# LB_BIT_1IN_2OUT-XXXL-v03_1_1x.net
KiCad netlist of a schematic drawn in EAGLE
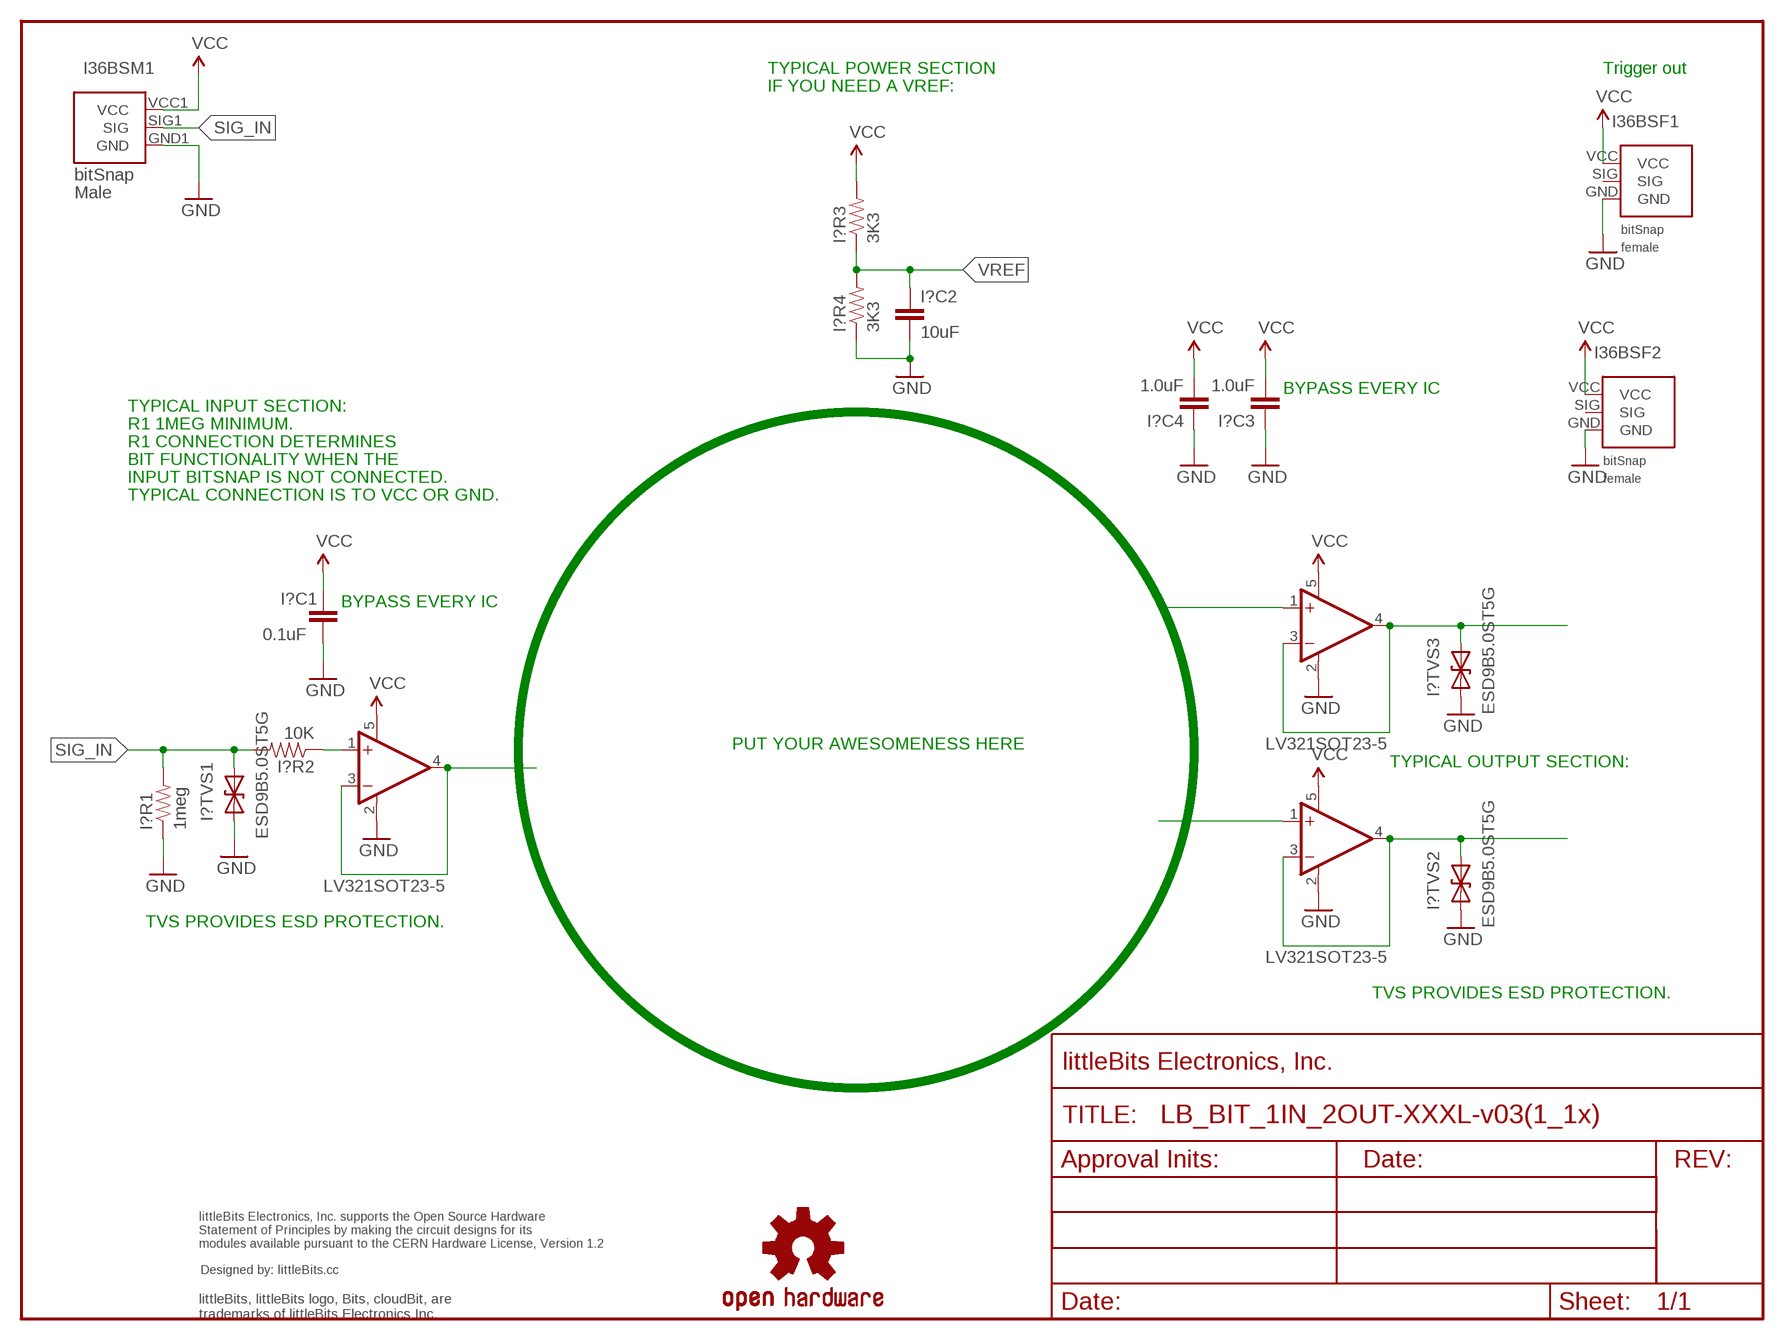
[diagram p0: schematic, sheet 1]

(export (version "E")
  (design (tool "Eeschema 10.0.6"))
  (components
    (comp (ref "FRAME1")
      (value "FRAME-LETTER")
      (footprint "eagle-import:FABDWG01-OHW")
      (libsource (lib "eagle-import") (part "FRAME-LETTER"))
    )
    (comp (ref "I36BSF1")
      (value "BITSNAP_V03_FEMALE")
      (footprint "eagle-import:BITSNAP_V03_FEMALE")
      (libsource (lib "eagle-import") (part "BITSNAP_V03_FEMALE"))
    )
    (comp (ref "I36BSF2")
      (value "BITSNAP_V03_FEMALE")
      (footprint "eagle-import:BITSNAP_V03_FEMALE")
      (libsource (lib "eagle-import") (part "BITSNAP_V03_FEMALE"))
    )
    (comp (ref "I36BSM1")
      (value "BITSNAP_V03_MALE")
      (footprint "eagle-import:BITSNAP_V03_MALE")
      (libsource (lib "eagle-import") (part "BITSNAP_V03_MALE"))
    )
    (comp (ref "I?C1")
      (value "0.1uF")
      (footprint "eagle-import:CAP-0603")
      (libsource (lib "eagle-import") (part "CAPCAP-0603"))
    )
    (comp (ref "I?C2")
      (value "10uF")
      (footprint "eagle-import:CAP-0603")
      (libsource (lib "eagle-import") (part "CAPCAP-0603"))
    )
    (comp (ref "I?C3")
      (value "1.0uF")
      (footprint "eagle-import:CAP-0603")
      (libsource (lib "eagle-import") (part "CAPCAP-0603"))
    )
    (comp (ref "I?C4")
      (value "1.0uF")
      (footprint "eagle-import:CAP-0603")
      (libsource (lib "eagle-import") (part "CAPCAP-0603"))
    )
    (comp (ref "I?R1")
      (value "1meg")
      (footprint "eagle-import:RES-0603")
      (libsource (lib "eagle-import") (part "RESISTOR0603"))
    )
    (comp (ref "I?R2")
      (value "10K")
      (footprint "eagle-import:RES-0603")
      (libsource (lib "eagle-import") (part "RESISTOR0603"))
    )
    (comp (ref "I?R3")
      (value "3K3")
      (footprint "eagle-import:RES-0603")
      (libsource (lib "eagle-import") (part "RESISTOR0603"))
    )
    (comp (ref "I?R4")
      (value "3K3")
      (footprint "eagle-import:RES-0603")
      (libsource (lib "eagle-import") (part "RESISTOR0603"))
    )
    (comp (ref "I?TVS1")
      (value "ESD9B5.0ST5G")
      (footprint "eagle-import:SOD-923")
      (libsource (lib "eagle-import") (part "DIODE-TVSSOD-923"))
    )
    (comp (ref "I?TVS2")
      (value "ESD9B5.0ST5G")
      (footprint "eagle-import:SOD-923")
      (libsource (lib "eagle-import") (part "DIODE-TVSSOD-923"))
    )
    (comp (ref "I?TVS3")
      (value "ESD9B5.0ST5G")
      (footprint "eagle-import:SOD-923")
      (libsource (lib "eagle-import") (part "DIODE-TVSSOD-923"))
    )
    (comp (ref "U$1")
      (value "OSHW-LOGOL")
      (footprint "eagle-import:OSHW-LOGO-L")
      (libsource (lib "eagle-import") (part "OSHW-LOGOL"))
    )
    (comp (ref "U$3")
      (value "OSHWCREDIT")
      (footprint "eagle-import:OSHWCREDIT")
      (libsource (lib "eagle-import") (part "OSHWCREDIT"))
    )
    (comp (ref "U1")
      (value "LV321SOT23-5")
      (footprint "eagle-import:SOT23-5")
      (libsource (lib "eagle-import") (part "LV321SOT23-5"))
    )
    (comp (ref "U2")
      (value "LV321SOT23-5")
      (footprint "eagle-import:SOT23-5")
      (libsource (lib "eagle-import") (part "LV321SOT23-5"))
    )
    (comp (ref "U3")
      (value "LV321SOT23-5")
      (footprint "eagle-import:SOT23-5")
      (libsource (lib "eagle-import") (part "LV321SOT23-5"))
    )
  )
  (nets
    (net (code "1") (name "GND") (class "Default")
      (node (ref "I36BSF1") (pin "GND") (pinfunction "GND_GND") (pintype "bidirectional"))
      (node (ref "I36BSF2") (pin "GND") (pinfunction "GND_GND") (pintype "bidirectional"))
      (node (ref "I36BSM1") (pin "GND1") (pinfunction "GND_GND1") (pintype "bidirectional"))
      (node (ref "I?C1") (pin "2") (pinfunction "2_2") (pintype "passive"))
      (node (ref "I?C2") (pin "2") (pinfunction "2_2") (pintype "passive"))
      (node (ref "I?C3") (pin "1") (pinfunction "1_1") (pintype "passive"))
      (node (ref "I?C4") (pin "1") (pinfunction "1_1") (pintype "passive"))
      (node (ref "I?R1") (pin "1") (pinfunction "1_1") (pintype "passive"))
      (node (ref "I?R4") (pin "1") (pinfunction "1_1") (pintype "passive"))
      (node (ref "I?TVS1") (pin "1") (pinfunction "A_1") (pintype "passive"))
      (node (ref "I?TVS2") (pin "1") (pinfunction "A_1") (pintype "passive"))
      (node (ref "I?TVS3") (pin "1") (pinfunction "A_1") (pintype "passive"))
      (node (ref "U1") (pin "2") (pinfunction "V-_2") (pintype "power_in"))
      (node (ref "U2") (pin "2") (pinfunction "V-_2") (pintype "power_in"))
      (node (ref "U3") (pin "2") (pinfunction "V-_2") (pintype "power_in"))
    )
    (net (code "2") (name "Net-(I?TVS2-C)") (class "Default")
      (node (ref "I?TVS2") (pin "2") (pinfunction "C_2") (pintype "passive"))
      (node (ref "U2") (pin "3") (pinfunction "-IN_3") (pintype "input"))
      (node (ref "U2") (pin "4") (pinfunction "OUT_4") (pintype "output"))
    )
    (net (code "3") (name "Net-(I?TVS3-C)") (class "Default")
      (node (ref "I?TVS3") (pin "2") (pinfunction "C_2") (pintype "passive"))
      (node (ref "U3") (pin "3") (pinfunction "-IN_3") (pintype "input"))
      (node (ref "U3") (pin "4") (pinfunction "OUT_4") (pintype "output"))
    )
    (net (code "4") (name "Net-(U1-+IN)") (class "Default")
      (node (ref "I?R2") (pin "1") (pinfunction "1_1") (pintype "passive"))
      (node (ref "U1") (pin "1") (pinfunction "+IN_1") (pintype "input"))
    )
    (net (code "5") (name "Net-(U1--IN)") (class "Default")
      (node (ref "U1") (pin "3") (pinfunction "-IN_3") (pintype "input"))
      (node (ref "U1") (pin "4") (pinfunction "OUT_4") (pintype "output"))
    )
    (net (code "6") (name "SIG_IN") (class "Default")
      (node (ref "I36BSM1") (pin "SIG1") (pinfunction "SIG_SIG1") (pintype "bidirectional"))
      (node (ref "I?R1") (pin "2") (pinfunction "2_2") (pintype "passive"))
      (node (ref "I?R2") (pin "2") (pinfunction "2_2") (pintype "passive"))
      (node (ref "I?TVS1") (pin "2") (pinfunction "C_2") (pintype "passive"))
    )
    (net (code "7") (name "VCC") (class "Default")
      (node (ref "I36BSF1") (pin "VCC") (pinfunction "VCC_VCC") (pintype "bidirectional"))
      (node (ref "I36BSF2") (pin "VCC") (pinfunction "VCC_VCC") (pintype "bidirectional"))
      (node (ref "I36BSM1") (pin "VCC1") (pinfunction "VCC_VCC1") (pintype "bidirectional"))
      (node (ref "I?C1") (pin "1") (pinfunction "1_1") (pintype "passive"))
      (node (ref "I?C3") (pin "2") (pinfunction "2_2") (pintype "passive"))
      (node (ref "I?C4") (pin "2") (pinfunction "2_2") (pintype "passive"))
      (node (ref "I?R3") (pin "2") (pinfunction "2_2") (pintype "passive"))
      (node (ref "U1") (pin "5") (pinfunction "V+_5") (pintype "power_in"))
      (node (ref "U2") (pin "5") (pinfunction "V+_5") (pintype "power_in"))
      (node (ref "U3") (pin "5") (pinfunction "V+_5") (pintype "power_in"))
    )
    (net (code "8") (name "VREF") (class "Default")
      (node (ref "I?C2") (pin "1") (pinfunction "1_1") (pintype "passive"))
      (node (ref "I?R3") (pin "1") (pinfunction "1_1") (pintype "passive"))
      (node (ref "I?R4") (pin "2") (pinfunction "2_2") (pintype "passive"))
    )
    (net (code "9") (name "unconnected-(I36BSF1-PadSIG)") (class "Default")
      (node (ref "I36BSF1") (pin "SIG") (pinfunction "SIG_SIG") (pintype "bidirectional"))
    )
    (net (code "10") (name "unconnected-(I36BSF2-PadSIG)") (class "Default")
      (node (ref "I36BSF2") (pin "SIG") (pinfunction "SIG_SIG") (pintype "bidirectional"))
    )
    (net (code "11") (name "unconnected-(U2-+IN-Pad1)") (class "Default")
      (node (ref "U2") (pin "1") (pinfunction "+IN_1") (pintype "input"))
    )
    (net (code "12") (name "unconnected-(U3-+IN-Pad1)") (class "Default")
      (node (ref "U3") (pin "1") (pinfunction "+IN_1") (pintype "input"))
    )
  )
)
